# AD9850_Board.net
KiCad netlist of a schematic drawn in EAGLE
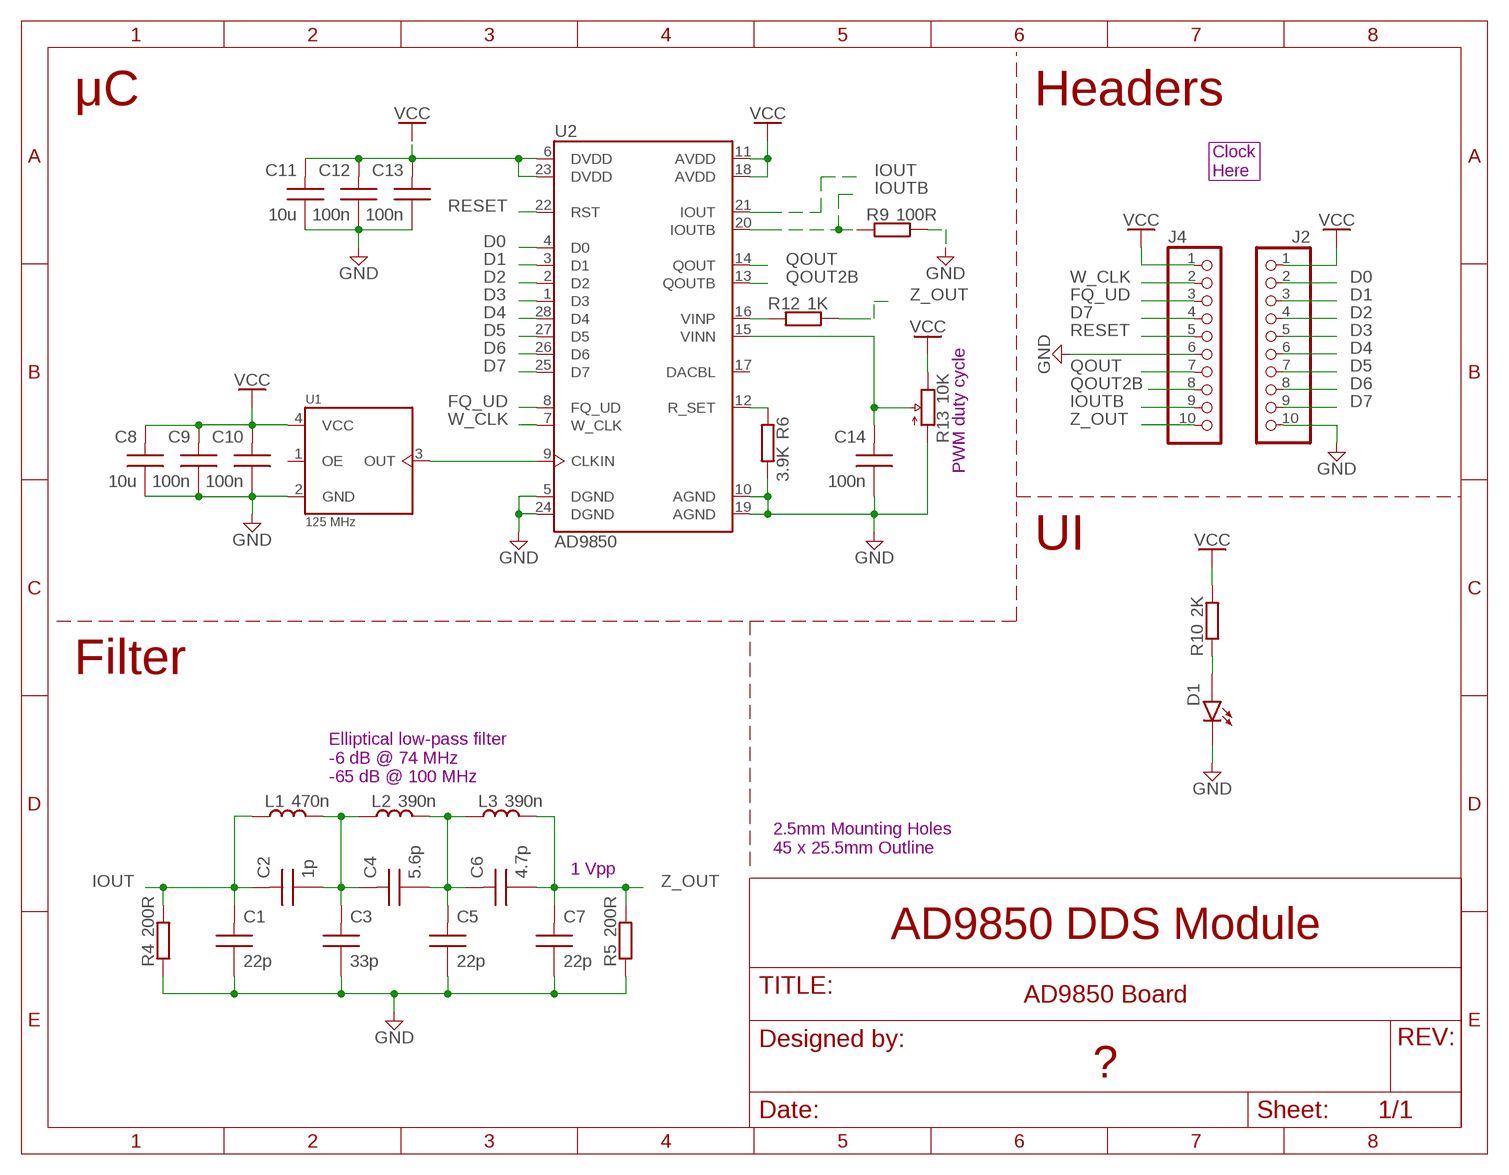
[diagram p0: schematic, sheet 1]

(export (version "E")
  (design (tool "Eeschema 10.0.6"))
  (components
    (comp (ref "C1")
      (value "22p")
      (footprint "eagle-import:SMT-0805")
      (libsource (lib "eagle-import") (part "CAPACITOR_0805"))
    )
    (comp (ref "C2")
      (value "1p")
      (footprint "eagle-import:SMT-0805")
      (libsource (lib "eagle-import") (part "CAPACITOR_0805"))
    )
    (comp (ref "C3")
      (value "33p")
      (footprint "eagle-import:SMT-0805")
      (libsource (lib "eagle-import") (part "CAPACITOR_0805"))
    )
    (comp (ref "C4")
      (value "5.6p")
      (footprint "eagle-import:SMT-0805")
      (libsource (lib "eagle-import") (part "CAPACITOR_0805"))
    )
    (comp (ref "C5")
      (value "22p")
      (footprint "eagle-import:SMT-0805")
      (libsource (lib "eagle-import") (part "CAPACITOR_0805"))
    )
    (comp (ref "C6")
      (value "4.7p")
      (footprint "eagle-import:SMT-0805")
      (libsource (lib "eagle-import") (part "CAPACITOR_0805"))
    )
    (comp (ref "C7")
      (value "22p")
      (footprint "eagle-import:SMT-0805")
      (libsource (lib "eagle-import") (part "CAPACITOR_0805"))
    )
    (comp (ref "C8")
      (value "10u")
      (footprint "eagle-import:SMT-0805")
      (libsource (lib "eagle-import") (part "CAPACITOR_0805"))
    )
    (comp (ref "C9")
      (value "100n")
      (footprint "eagle-import:SMT-0805")
      (libsource (lib "eagle-import") (part "CAPACITOR_0805"))
    )
    (comp (ref "C10")
      (value "100n")
      (footprint "eagle-import:SMT-0805")
      (libsource (lib "eagle-import") (part "CAPACITOR_0805"))
    )
    (comp (ref "C11")
      (value "10u")
      (footprint "eagle-import:SMT-0805")
      (libsource (lib "eagle-import") (part "CAPACITOR_0805"))
    )
    (comp (ref "C12")
      (value "100n")
      (footprint "eagle-import:SMT-0805")
      (libsource (lib "eagle-import") (part "CAPACITOR_0805"))
    )
    (comp (ref "C13")
      (value "100n")
      (footprint "eagle-import:SMT-0805")
      (libsource (lib "eagle-import") (part "CAPACITOR_0805"))
    )
    (comp (ref "C14")
      (value "100n")
      (footprint "eagle-import:SMT-0805")
      (libsource (lib "eagle-import") (part "CAPACITOR_0805"))
    )
    (comp (ref "D1")
      (value "LED_0805")
      (footprint "eagle-import:SMT-0805-LED")
      (libsource (lib "eagle-import") (part "LED_0805"))
    )
    (comp (ref "J2")
      (value "HEADER-1X10")
      (footprint "eagle-import:1X10")
      (libsource (lib "eagle-import") (part "HEADER-1X10"))
    )
    (comp (ref "J4")
      (value "HEADER-1X10")
      (footprint "eagle-import:1X10")
      (libsource (lib "eagle-import") (part "HEADER-1X10"))
    )
    (comp (ref "L1")
      (value "470n")
      (footprint "eagle-import:SMT-0805")
      (libsource (lib "eagle-import") (part "INDUCTOR"))
    )
    (comp (ref "L2")
      (value "390n")
      (footprint "eagle-import:SMT-0805")
      (libsource (lib "eagle-import") (part "INDUCTOR"))
    )
    (comp (ref "L3")
      (value "390n")
      (footprint "eagle-import:SMT-0805")
      (libsource (lib "eagle-import") (part "INDUCTOR"))
    )
    (comp (ref "R4")
      (value "200R")
      (footprint "eagle-import:SMT-0805")
      (libsource (lib "eagle-import") (part "RESISTOR_SMT-0805"))
    )
    (comp (ref "R5")
      (value "200R")
      (footprint "eagle-import:SMT-0805")
      (libsource (lib "eagle-import") (part "RESISTOR_SMT-0805"))
    )
    (comp (ref "R6")
      (value "3.9K")
      (footprint "eagle-import:SMT-0805")
      (libsource (lib "eagle-import") (part "RESISTOR_SMT-0805"))
    )
    (comp (ref "R9")
      (value "100R")
      (footprint "eagle-import:SMT-0805")
      (libsource (lib "eagle-import") (part "RESISTOR_SMT-0805"))
    )
    (comp (ref "R10")
      (value "2K")
      (footprint "eagle-import:SMT-0805")
      (libsource (lib "eagle-import") (part "RESISTOR_SMT-0805"))
    )
    (comp (ref "R12")
      (value "1K")
      (footprint "eagle-import:SMT-0805")
      (libsource (lib "eagle-import") (part "RESISTOR_SMT-0805"))
    )
    (comp (ref "R13")
      (value "10K")
      (footprint "eagle-import:TH-100MIL-RESISTOR-VAR")
      (libsource (lib "eagle-import") (part "RESISTOR-VAR"))
    )
    (comp (ref "U1")
      (value "125 MHz")
      (footprint "eagle-import:PLACEHOLDER4")
      (libsource (lib "eagle-import") (part "CLOCK"))
    )
    (comp (ref "U2")
      (value "AD9850")
      (footprint "eagle-import:TSSOP28-0.65MM")
      (libsource (lib "eagle-import") (part "AD9850"))
    )
  )
  (nets
    (net (code "1") (name "/D0") (class "Default")
      (node (ref "J2") (pin "2") (pinfunction "2_2") (pintype "passive"))
      (node (ref "U2") (pin "4") (pinfunction "D0_4") (pintype "input"))
    )
    (net (code "2") (name "/D1") (class "Default")
      (node (ref "J2") (pin "3") (pinfunction "3_3") (pintype "passive"))
      (node (ref "U2") (pin "3") (pinfunction "D1_3") (pintype "input"))
    )
    (net (code "3") (name "/D2") (class "Default")
      (node (ref "J2") (pin "4") (pinfunction "4_4") (pintype "passive"))
      (node (ref "U2") (pin "2") (pinfunction "D2_2") (pintype "input"))
    )
    (net (code "4") (name "/D3") (class "Default")
      (node (ref "J2") (pin "5") (pinfunction "5_5") (pintype "passive"))
      (node (ref "U2") (pin "1") (pinfunction "D3_1") (pintype "input"))
    )
    (net (code "5") (name "/D4") (class "Default")
      (node (ref "J2") (pin "6") (pinfunction "6_6") (pintype "passive"))
      (node (ref "U2") (pin "28") (pinfunction "D4_28") (pintype "input"))
    )
    (net (code "6") (name "/D5") (class "Default")
      (node (ref "J2") (pin "7") (pinfunction "7_7") (pintype "passive"))
      (node (ref "U2") (pin "27") (pinfunction "D5_27") (pintype "input"))
    )
    (net (code "7") (name "/D6") (class "Default")
      (node (ref "J2") (pin "8") (pinfunction "8_8") (pintype "passive"))
      (node (ref "U2") (pin "26") (pinfunction "D6_26") (pintype "input"))
    )
    (net (code "8") (name "/D7") (class "Default")
      (node (ref "J2") (pin "9") (pinfunction "9_9") (pintype "passive"))
      (node (ref "J4") (pin "4") (pinfunction "4_4") (pintype "passive"))
      (node (ref "U2") (pin "25") (pinfunction "D7_25") (pintype "input"))
    )
    (net (code "9") (name "/FQ_UD") (class "Default")
      (node (ref "J4") (pin "3") (pinfunction "3_3") (pintype "passive"))
      (node (ref "U2") (pin "8") (pinfunction "FQ_UD_8") (pintype "input"))
    )
    (net (code "10") (name "/IOUT") (class "Default")
      (node (ref "C1") (pin "P$1") (pinfunction "P$1_P$1") (pintype "bidirectional"))
      (node (ref "C2") (pin "P$1") (pinfunction "P$1_P$1") (pintype "bidirectional"))
      (node (ref "L1") (pin "P$1") (pinfunction "P$1_P$1") (pintype "passive"))
      (node (ref "R4") (pin "P$2") (pinfunction "P$2_P$2") (pintype "bidirectional"))
      (node (ref "U2") (pin "21") (pinfunction "IOUT_21") (pintype "output"))
    )
    (net (code "11") (name "/IOUTB") (class "Default")
      (node (ref "J4") (pin "9") (pinfunction "9_9") (pintype "passive"))
      (node (ref "R9") (pin "P$1") (pinfunction "P$1_P$1") (pintype "bidirectional"))
      (node (ref "U2") (pin "20") (pinfunction "IOUTB_20") (pintype "output"))
    )
    (net (code "12") (name "/QOUT") (class "Default")
      (node (ref "J4") (pin "7") (pinfunction "7_7") (pintype "passive"))
      (node (ref "U2") (pin "14") (pinfunction "QOUT_14") (pintype "output"))
    )
    (net (code "13") (name "/QOUT2B") (class "Default")
      (node (ref "J4") (pin "8") (pinfunction "8_8") (pintype "passive"))
      (node (ref "U2") (pin "13") (pinfunction "QOUTB_13") (pintype "output"))
    )
    (net (code "14") (name "/RESET") (class "Default")
      (node (ref "J4") (pin "5") (pinfunction "5_5") (pintype "passive"))
      (node (ref "U2") (pin "22") (pinfunction "RST_22") (pintype "bidirectional"))
    )
    (net (code "15") (name "/W_CLK") (class "Default")
      (node (ref "J4") (pin "2") (pinfunction "2_2") (pintype "passive"))
      (node (ref "U2") (pin "7") (pinfunction "W_CLK_7") (pintype "input"))
    )
    (net (code "16") (name "/Z_OUT") (class "Default")
      (node (ref "C6") (pin "P$2") (pinfunction "P$2_P$2") (pintype "bidirectional"))
      (node (ref "C7") (pin "P$1") (pinfunction "P$1_P$1") (pintype "bidirectional"))
      (node (ref "J4") (pin "10") (pinfunction "10_10") (pintype "passive"))
      (node (ref "L3") (pin "P$2") (pinfunction "P$2_P$2") (pintype "passive"))
      (node (ref "R12") (pin "P$2") (pinfunction "P$2_P$2") (pintype "bidirectional"))
      (node (ref "R5") (pin "P$2") (pinfunction "P$2_P$2") (pintype "bidirectional"))
    )
    (net (code "17") (name "GND") (class "Default")
      (node (ref "C1") (pin "P$2") (pinfunction "P$2_P$2") (pintype "bidirectional"))
      (node (ref "C10") (pin "P$2") (pinfunction "P$2_P$2") (pintype "bidirectional"))
      (node (ref "C11") (pin "P$2") (pinfunction "P$2_P$2") (pintype "bidirectional"))
      (node (ref "C12") (pin "P$2") (pinfunction "P$2_P$2") (pintype "bidirectional"))
      (node (ref "C13") (pin "P$2") (pinfunction "P$2_P$2") (pintype "bidirectional"))
      (node (ref "C14") (pin "P$2") (pinfunction "P$2_P$2") (pintype "bidirectional"))
      (node (ref "C3") (pin "P$2") (pinfunction "P$2_P$2") (pintype "bidirectional"))
      (node (ref "C5") (pin "P$2") (pinfunction "P$2_P$2") (pintype "bidirectional"))
      (node (ref "C7") (pin "P$2") (pinfunction "P$2_P$2") (pintype "bidirectional"))
      (node (ref "C8") (pin "P$2") (pinfunction "P$2_P$2") (pintype "bidirectional"))
      (node (ref "C9") (pin "P$2") (pinfunction "P$2_P$2") (pintype "bidirectional"))
      (node (ref "D1") (pin "C") (pinfunction "CATHODE_C") (pintype "bidirectional"))
      (node (ref "J2") (pin "10") (pinfunction "10_10") (pintype "passive"))
      (node (ref "J4") (pin "6") (pinfunction "6_6") (pintype "passive"))
      (node (ref "R13") (pin "CCW") (pinfunction "CCW_CCW") (pintype "bidirectional"))
      (node (ref "R4") (pin "P$1") (pinfunction "P$1_P$1") (pintype "bidirectional"))
      (node (ref "R5") (pin "P$1") (pinfunction "P$1_P$1") (pintype "bidirectional"))
      (node (ref "R6") (pin "P$2") (pinfunction "P$2_P$2") (pintype "bidirectional"))
      (node (ref "R9") (pin "P$2") (pinfunction "P$2_P$2") (pintype "bidirectional"))
      (node (ref "U1") (pin "2") (pinfunction "GND_2") (pintype "power_in"))
      (node (ref "U2") (pin "10") (pinfunction "AGND_10") (pintype "power_in"))
      (node (ref "U2") (pin "19") (pinfunction "AGND_19") (pintype "power_in"))
      (node (ref "U2") (pin "24") (pinfunction "DGND_24") (pintype "power_in"))
      (node (ref "U2") (pin "5") (pinfunction "DGND_5") (pintype "power_in"))
    )
    (net (code "18") (name "Net-(C2-PadP$2)") (class "Default")
      (node (ref "C2") (pin "P$2") (pinfunction "P$2_P$2") (pintype "bidirectional"))
      (node (ref "C3") (pin "P$1") (pinfunction "P$1_P$1") (pintype "bidirectional"))
      (node (ref "C4") (pin "P$1") (pinfunction "P$1_P$1") (pintype "bidirectional"))
      (node (ref "L1") (pin "P$2") (pinfunction "P$2_P$2") (pintype "passive"))
      (node (ref "L2") (pin "P$1") (pinfunction "P$1_P$1") (pintype "passive"))
    )
    (net (code "19") (name "Net-(C4-PadP$2)") (class "Default")
      (node (ref "C4") (pin "P$2") (pinfunction "P$2_P$2") (pintype "bidirectional"))
      (node (ref "C5") (pin "P$1") (pinfunction "P$1_P$1") (pintype "bidirectional"))
      (node (ref "C6") (pin "P$1") (pinfunction "P$1_P$1") (pintype "bidirectional"))
      (node (ref "L2") (pin "P$2") (pinfunction "P$2_P$2") (pintype "passive"))
      (node (ref "L3") (pin "P$1") (pinfunction "P$1_P$1") (pintype "passive"))
    )
    (net (code "20") (name "Net-(D1-ANODE)") (class "Default")
      (node (ref "D1") (pin "A") (pinfunction "ANODE_A") (pintype "bidirectional"))
      (node (ref "R10") (pin "P$1") (pinfunction "P$1_P$1") (pintype "bidirectional"))
    )
    (net (code "21") (name "Net-(U1-OUT)") (class "Default")
      (node (ref "U1") (pin "3") (pinfunction "OUT_3") (pintype "output"))
      (node (ref "U2") (pin "9") (pinfunction "CLKIN_9") (pintype "input"))
    )
    (net (code "22") (name "Net-(U2-R_SET)") (class "Default")
      (node (ref "R6") (pin "P$1") (pinfunction "P$1_P$1") (pintype "bidirectional"))
      (node (ref "U2") (pin "12") (pinfunction "R_SET_12") (pintype "output"))
    )
    (net (code "23") (name "Net-(U2-VINN)") (class "Default")
      (node (ref "C14") (pin "P$1") (pinfunction "P$1_P$1") (pintype "bidirectional"))
      (node (ref "R13") (pin "WIPER") (pinfunction "WIPER_WIPER") (pintype "bidirectional"))
      (node (ref "U2") (pin "15") (pinfunction "VINN_15") (pintype "input"))
    )
    (net (code "24") (name "Net-(U2-VINP)") (class "Default")
      (node (ref "R12") (pin "P$1") (pinfunction "P$1_P$1") (pintype "bidirectional"))
      (node (ref "U2") (pin "16") (pinfunction "VINP_16") (pintype "input"))
    )
    (net (code "25") (name "VCC") (class "Default")
      (node (ref "C10") (pin "P$1") (pinfunction "P$1_P$1") (pintype "bidirectional"))
      (node (ref "C11") (pin "P$1") (pinfunction "P$1_P$1") (pintype "bidirectional"))
      (node (ref "C12") (pin "P$1") (pinfunction "P$1_P$1") (pintype "bidirectional"))
      (node (ref "C13") (pin "P$1") (pinfunction "P$1_P$1") (pintype "bidirectional"))
      (node (ref "C8") (pin "P$1") (pinfunction "P$1_P$1") (pintype "bidirectional"))
      (node (ref "C9") (pin "P$1") (pinfunction "P$1_P$1") (pintype "bidirectional"))
      (node (ref "J2") (pin "1") (pinfunction "1_1") (pintype "passive"))
      (node (ref "J4") (pin "1") (pinfunction "1_1") (pintype "passive"))
      (node (ref "R10") (pin "P$2") (pinfunction "P$2_P$2") (pintype "bidirectional"))
      (node (ref "R13") (pin "CW") (pinfunction "CW_CW") (pintype "bidirectional"))
      (node (ref "U1") (pin "4") (pinfunction "VCC_4") (pintype "power_in"))
      (node (ref "U2") (pin "11") (pinfunction "AVDD_11") (pintype "power_in"))
      (node (ref "U2") (pin "18") (pinfunction "AVDD_18") (pintype "power_in"))
      (node (ref "U2") (pin "23") (pinfunction "DVDD_23") (pintype "power_in"))
      (node (ref "U2") (pin "6") (pinfunction "DVDD_6") (pintype "power_in"))
    )
    (net (code "26") (name "unconnected-(U1-OE-Pad1)") (class "Default")
      (node (ref "U1") (pin "1") (pinfunction "OE_1") (pintype "input"))
    )
    (net (code "27") (name "unconnected-(U2-DACBL-Pad17)") (class "Default")
      (node (ref "U2") (pin "17") (pinfunction "DACBL_17") (pintype "no_connect"))
    )
  )
)
